# Nu2031.net
KiCad netlist of a schematic drawn in EAGLE
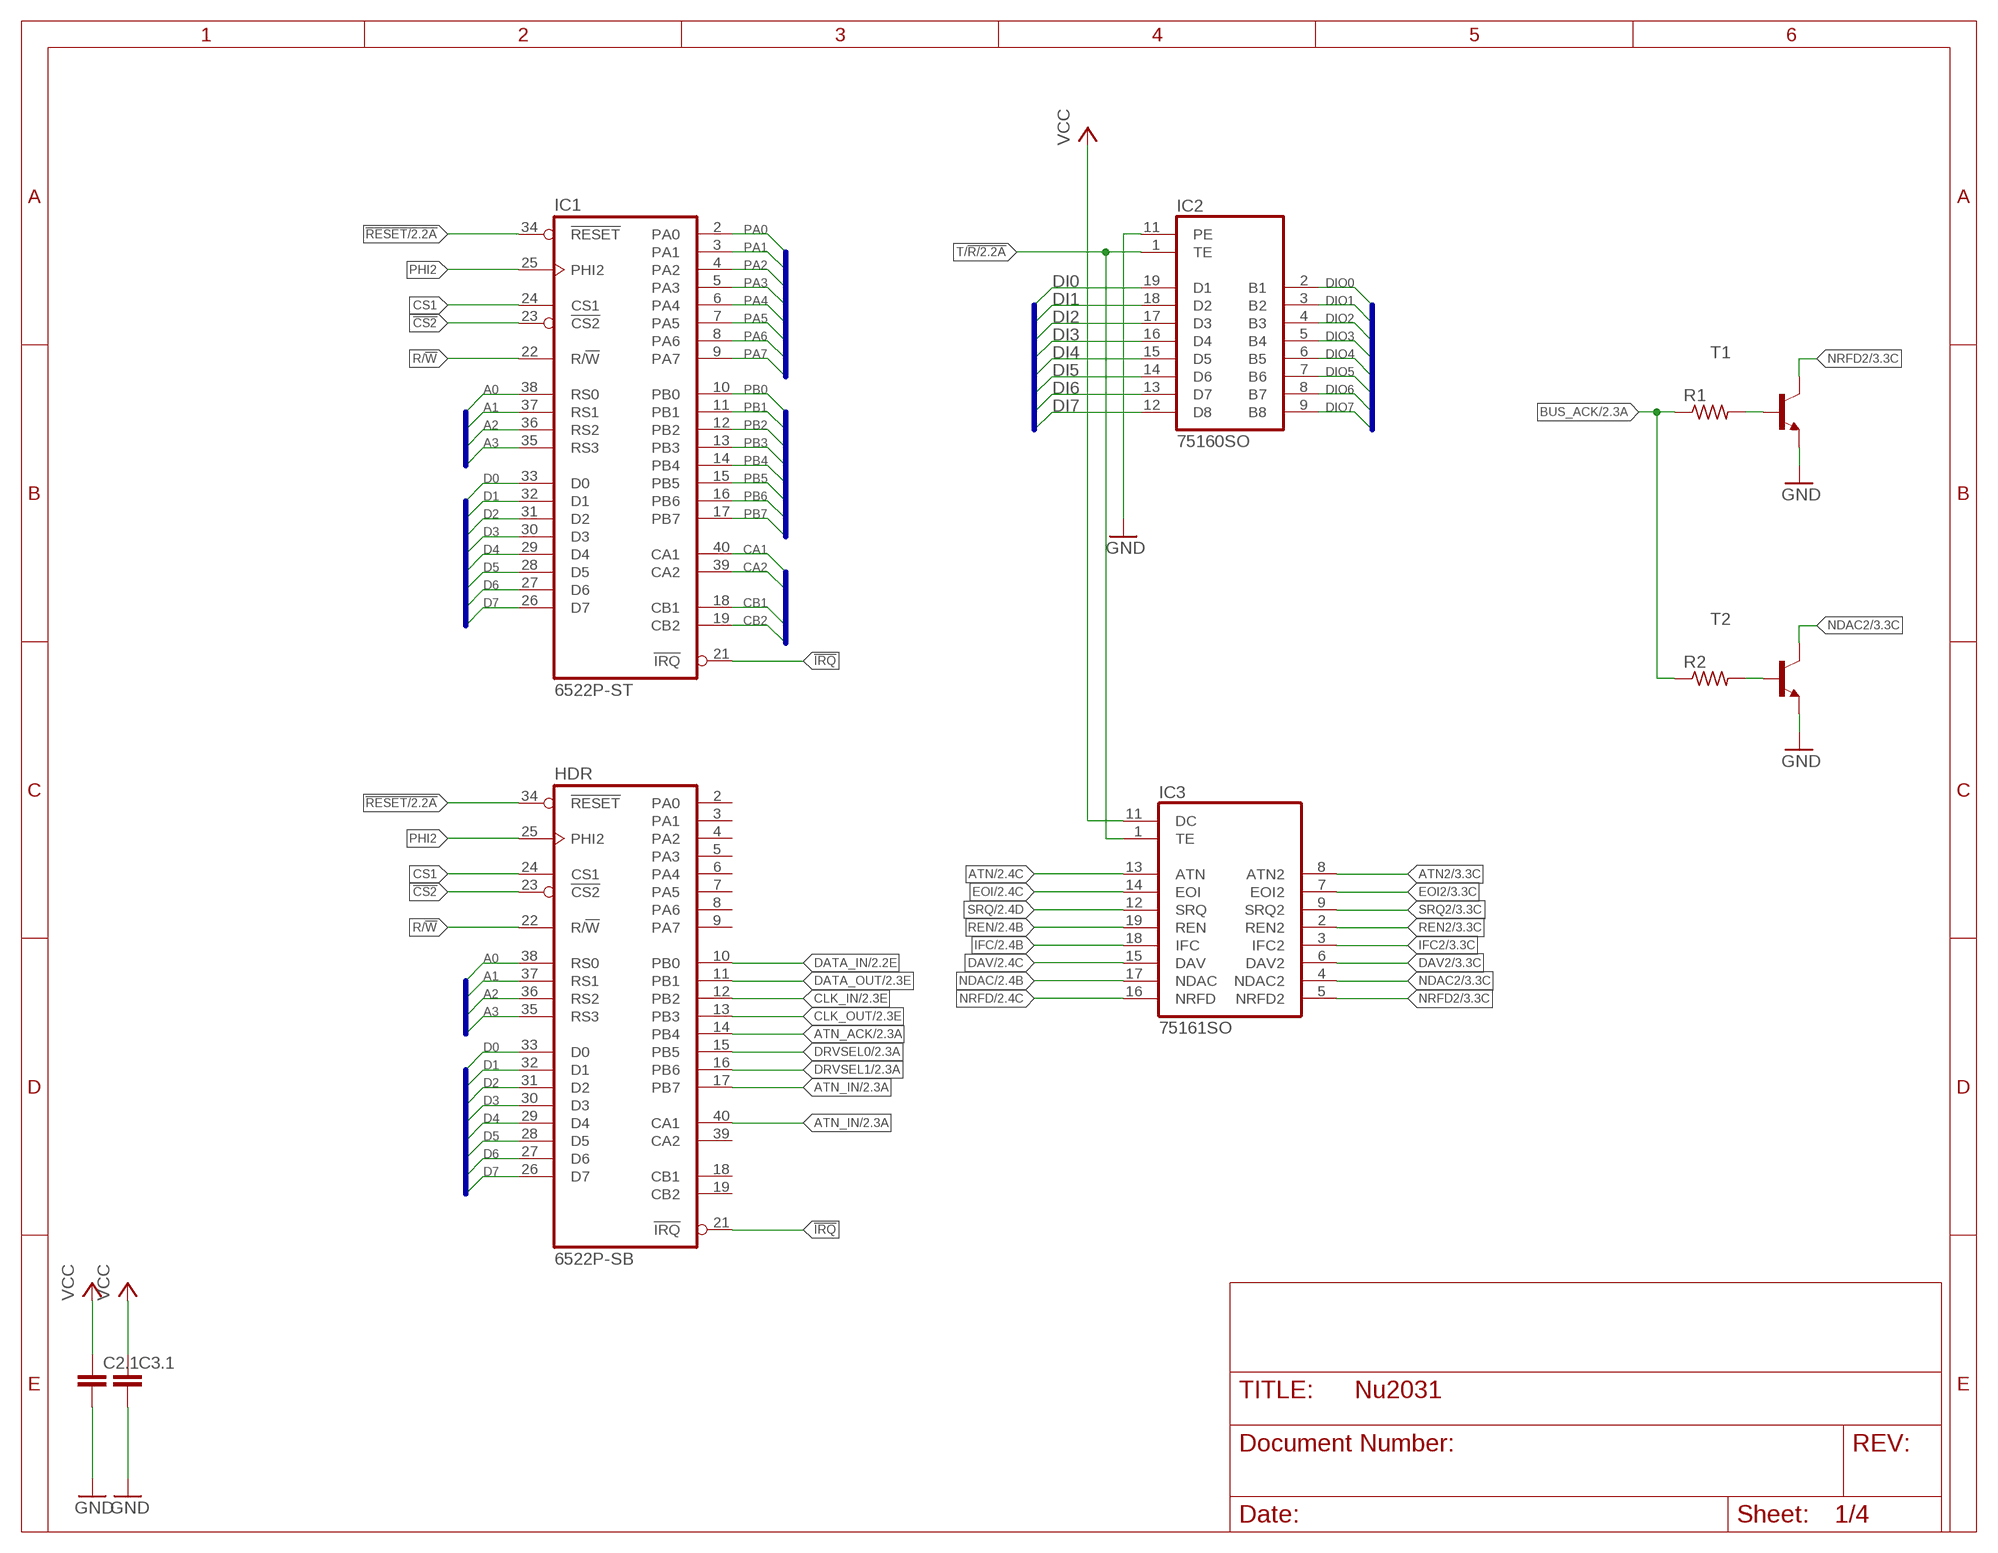
[diagram p0: schematic, sheet 1]
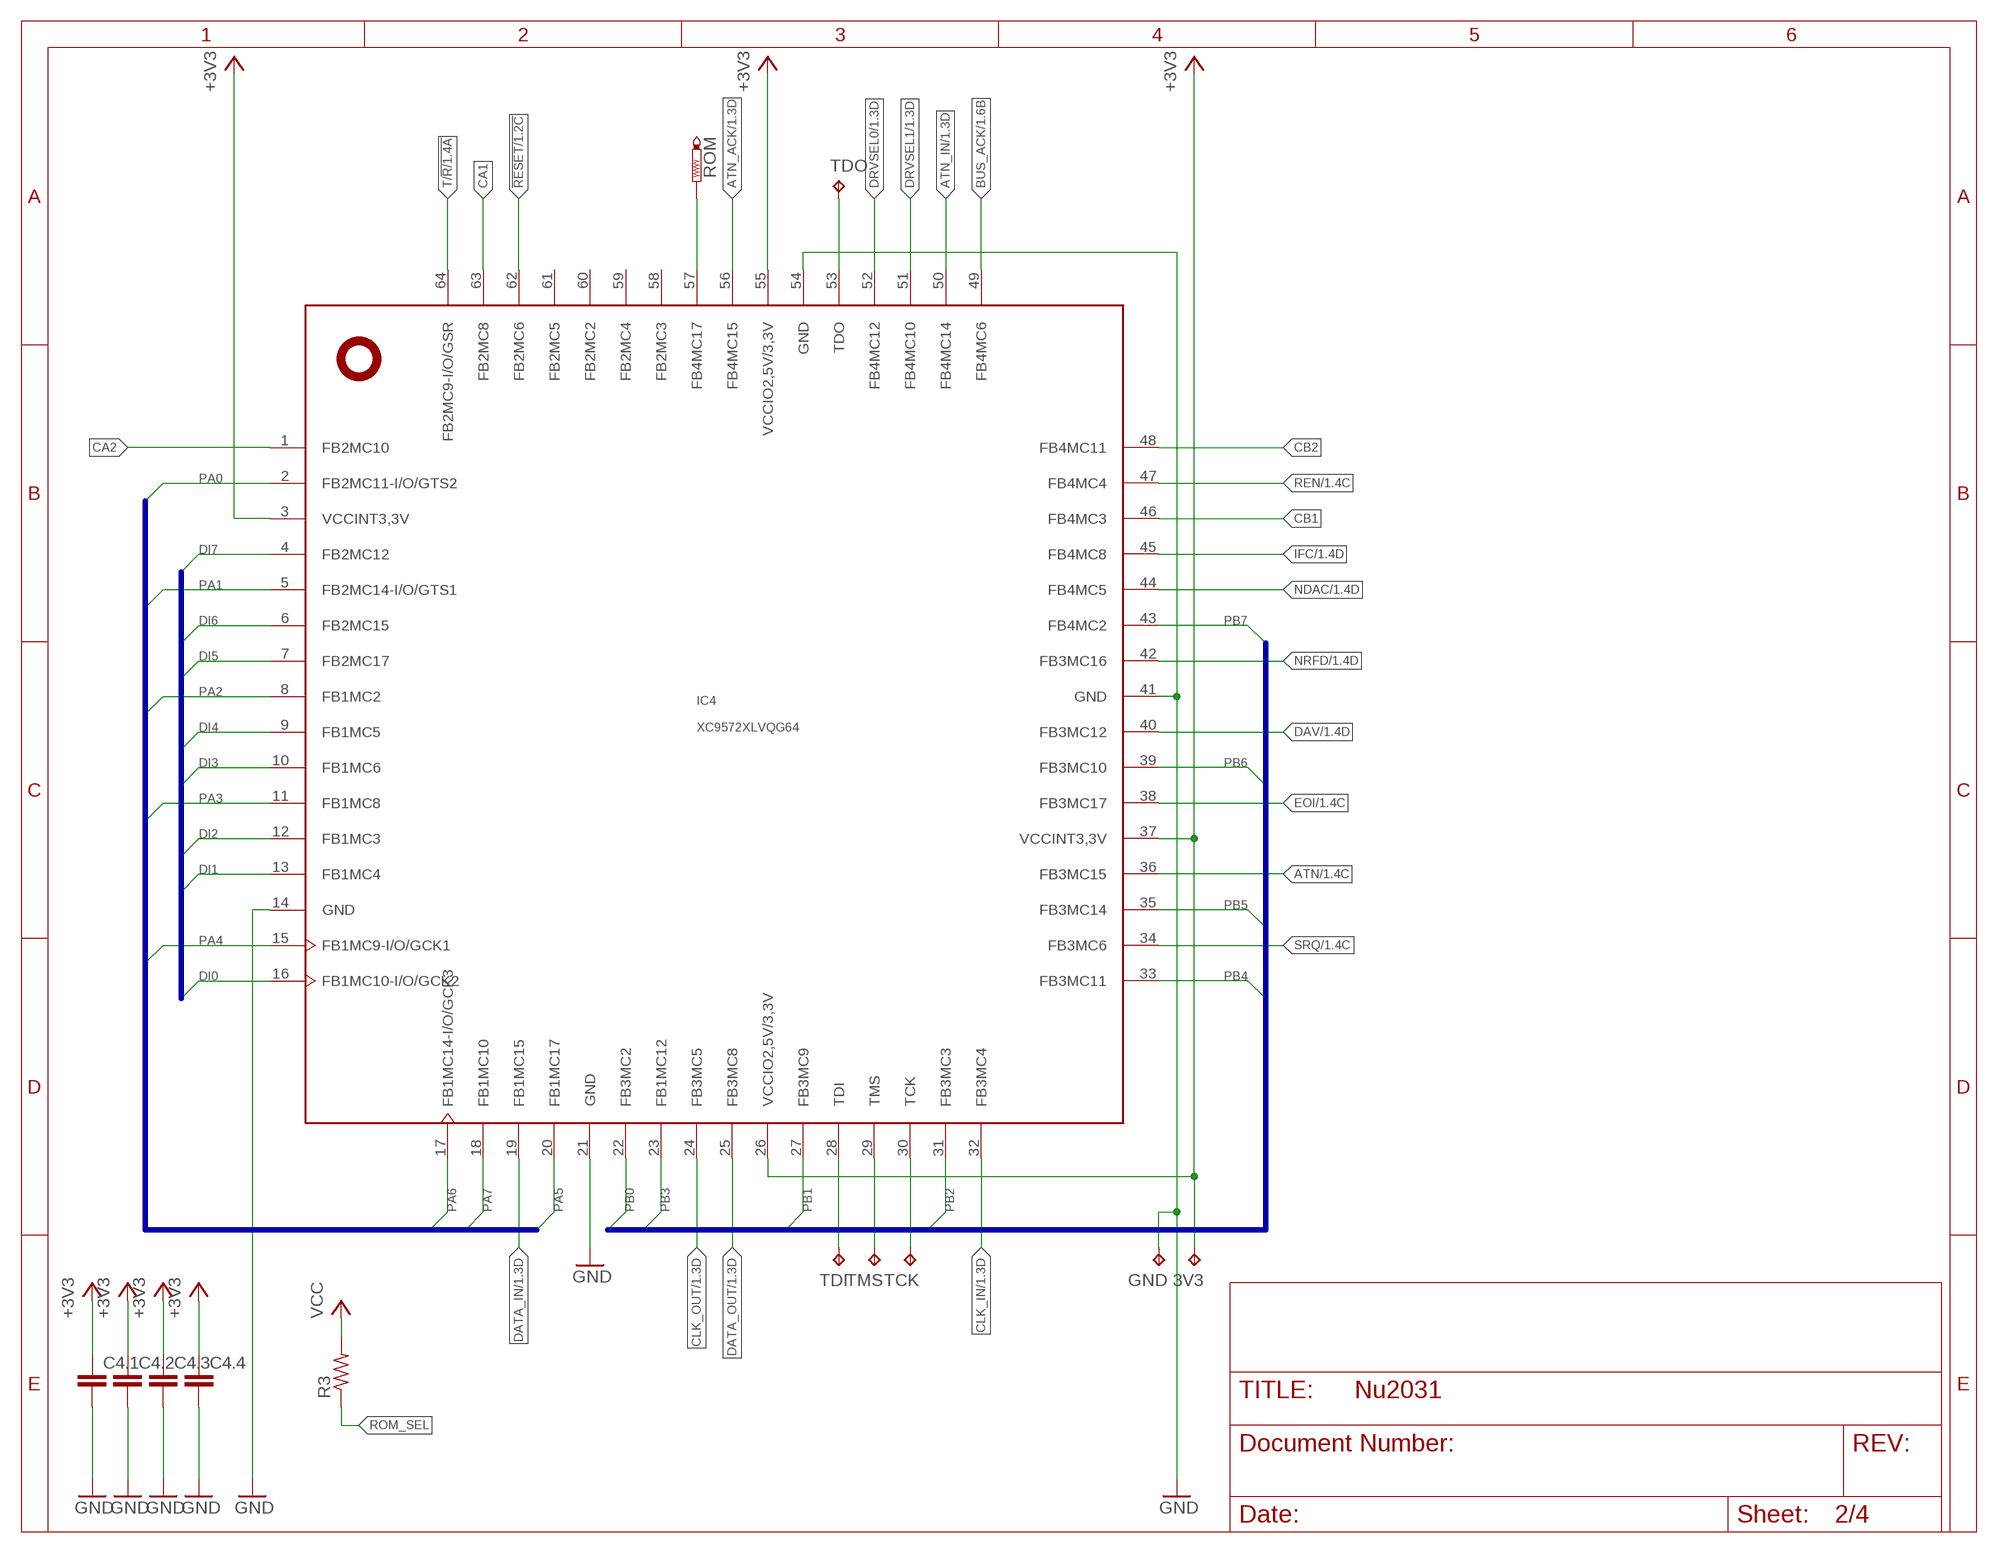
[diagram p1: schematic, sheet 2]
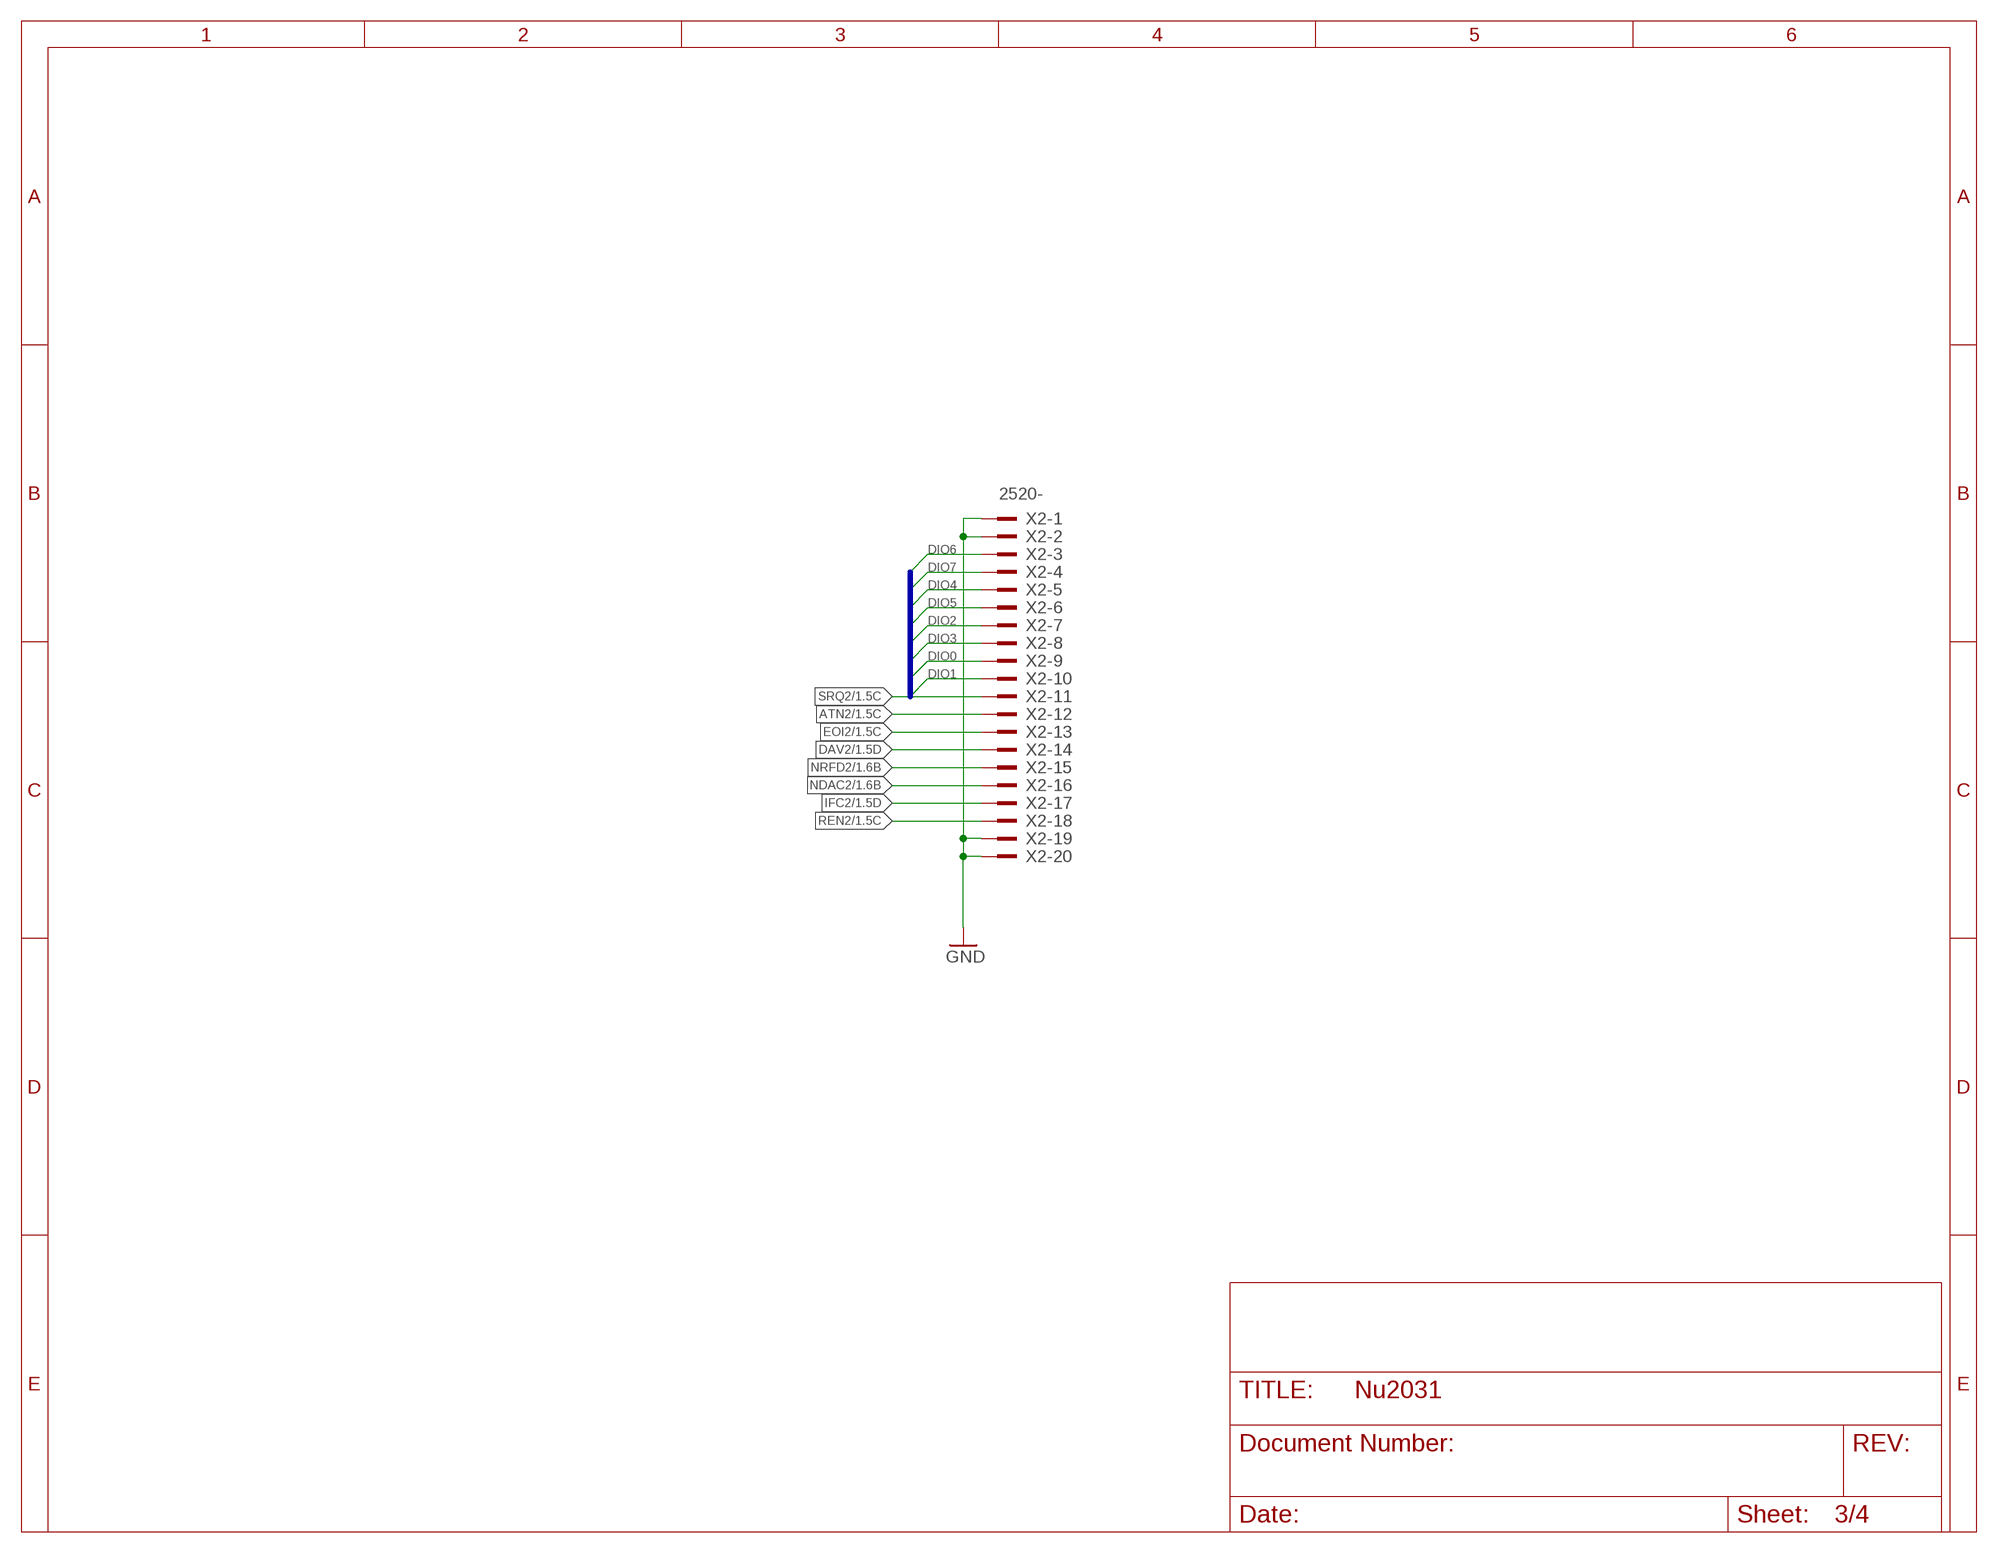
[diagram p2: schematic, sheet 3]
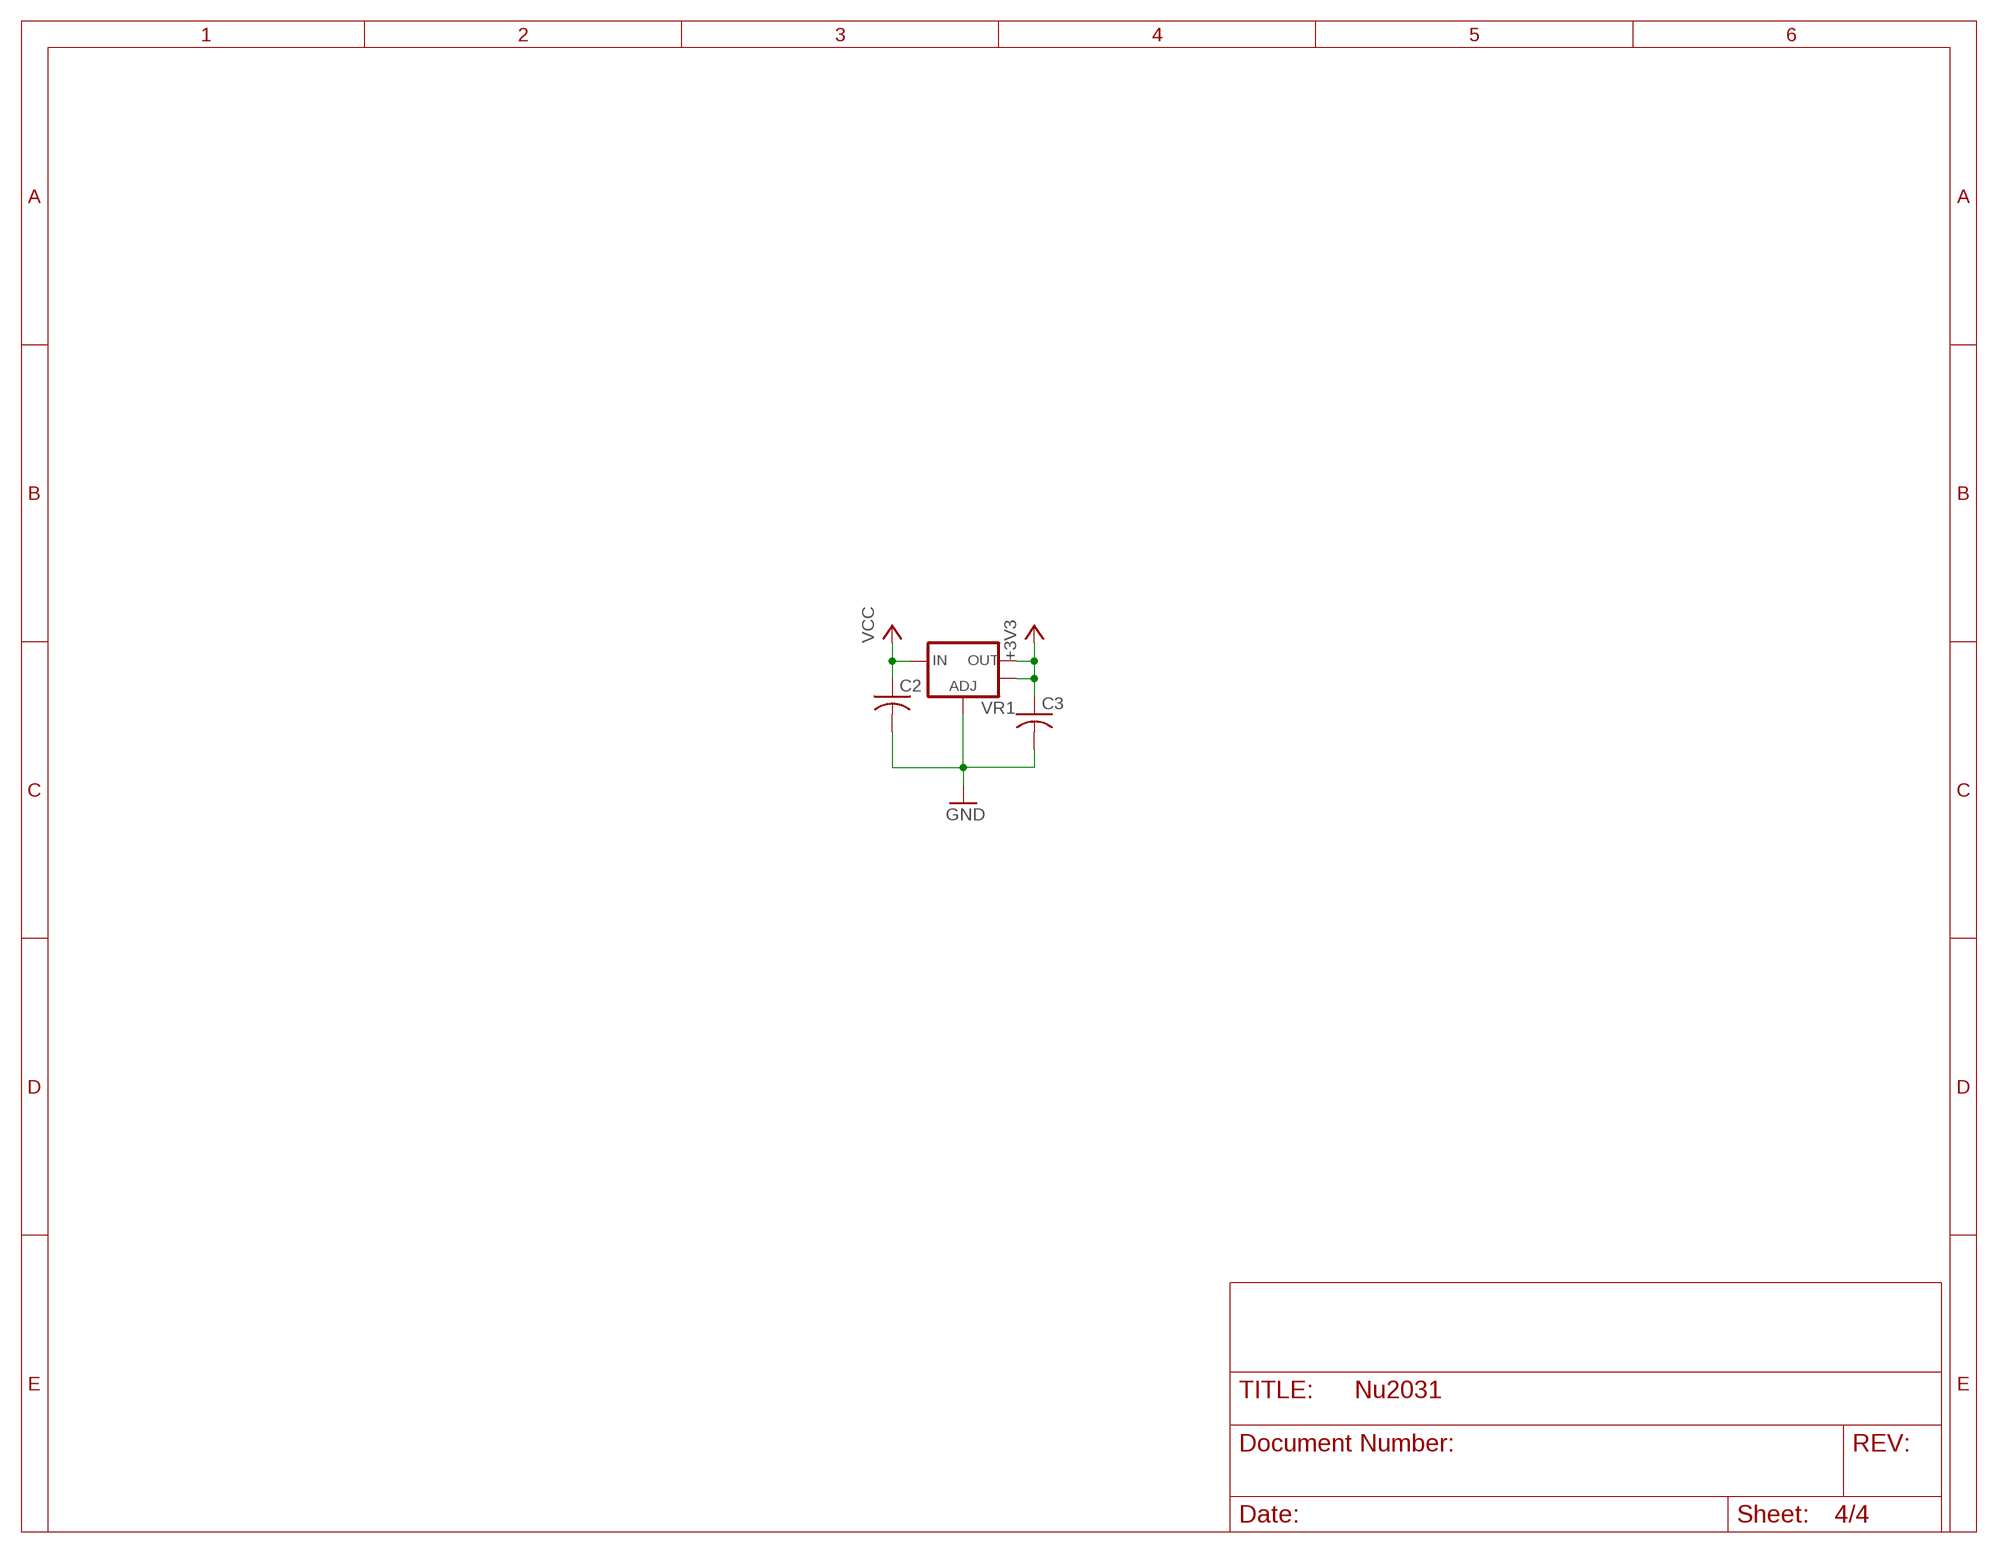
[diagram p3: schematic, sheet 4]

(export (version "E")
  (design (tool "Eeschema 10.0.6"))
  (components
    (comp (ref "X2")
      (value "2520-")
      (footprint "eagle-import:PAK100_2500-20")
      (libsource (lib "eagle-import") (part "2520-"))
    )
    (comp (ref "C2.1")
      (value "C-EUC0402")
      (footprint "eagle-import:C0402")
      (libsource (lib "eagle-import") (part "C-EUC0402"))
    )
    (comp (ref "C3.1")
      (value "C-EUC0402")
      (footprint "eagle-import:C0402")
      (libsource (lib "eagle-import") (part "C-EUC0402"))
    )
    (comp (ref "HDR")
      (value "6522P-SB")
      (footprint "eagle-import:DIL40-SMD-REVERSE")
      (libsource (lib "eagle-import") (part "6522P-SB"))
    )
    (comp (ref "IC1")
      (value "6522P-ST")
      (footprint "eagle-import:DIL40-SMD")
      (libsource (lib "eagle-import") (part "6522P-ST"))
    )
    (comp (ref "IC2")
      (value "75160SO")
      (footprint "eagle-import:SO20L")
      (libsource (lib "eagle-import") (part "75160SO"))
    )
    (comp (ref "IC3")
      (value "75161SO")
      (footprint "eagle-import:SO20L")
      (libsource (lib "eagle-import") (part "75161SO"))
    )
    (comp (ref "R1")
      (value "R-US_R0402")
      (footprint "eagle-import:R0402")
      (libsource (lib "eagle-import") (part "R-US_R0402"))
    )
    (comp (ref "R2")
      (value "R-US_R0402")
      (footprint "eagle-import:R0402")
      (libsource (lib "eagle-import") (part "R-US_R0402"))
    )
    (comp (ref "T1")
      (value "MMBT3904LT1-NPN-SOT23-BEC")
      (footprint "eagle-import:SOT23-BEC")
      (libsource (lib "eagle-import") (part "-NPN-SOT23-BECMMBT3904LT1"))
    )
    (comp (ref "T2")
      (value "MMBT3904LT1-NPN-SOT23-BEC")
      (footprint "eagle-import:SOT23-BEC")
      (libsource (lib "eagle-import") (part "-NPN-SOT23-BECMMBT3904LT1"))
    )
    (comp (ref "C2")
      (value "C-USC0805")
      (footprint "eagle-import:C0805")
      (libsource (lib "eagle-import") (part "C-USC0805"))
    )
    (comp (ref "C3")
      (value "C-USC0805")
      (footprint "eagle-import:C0805")
      (libsource (lib "eagle-import") (part "C-USC0805"))
    )
    (comp (ref "VR1")
      (value "V_REG_LM1117SOT223")
      (footprint "eagle-import:SOT223")
      (libsource (lib "eagle-import") (part "V_REG_LM1117SOT223"))
    )
    (comp (ref "3V3")
      (value "TPTP10R")
      (footprint "eagle-import:TP10R")
      (libsource (lib "eagle-import") (part "TPTP10R"))
    )
    (comp (ref "C4.1")
      (value "C-EUC0402")
      (footprint "eagle-import:C0402")
      (libsource (lib "eagle-import") (part "C-EUC0402"))
    )
    (comp (ref "C4.2")
      (value "C-EUC0402")
      (footprint "eagle-import:C0402")
      (libsource (lib "eagle-import") (part "C-EUC0402"))
    )
    (comp (ref "C4.3")
      (value "C-EUC0402")
      (footprint "eagle-import:C0402")
      (libsource (lib "eagle-import") (part "C-EUC0402"))
    )
    (comp (ref "C4.4")
      (value "C-EUC0402")
      (footprint "eagle-import:C0402")
      (libsource (lib "eagle-import") (part "C-EUC0402"))
    )
    (comp (ref "GND")
      (value "TPTP10R")
      (footprint "eagle-import:TP10R")
      (libsource (lib "eagle-import") (part "TPTP10R"))
    )
    (comp (ref "IC4")
      (value "XC9572XLVQG64")
      (footprint "eagle-import:VQFP64")
      (libsource (lib "eagle-import") (part "XC9572XLVQG64"))
    )
    (comp (ref "R3")
      (value "R-US_R0402")
      (footprint "eagle-import:R0402")
      (libsource (lib "eagle-import") (part "R-US_R0402"))
    )
    (comp (ref "ROM")
      (value "PTR1B1,27")
      (footprint "eagle-import:B1,27")
      (libsource (lib "eagle-import") (part "PTR1B1,27"))
    )
    (comp (ref "TCK")
      (value "TPTP10R")
      (footprint "eagle-import:TP10R")
      (libsource (lib "eagle-import") (part "TPTP10R"))
    )
    (comp (ref "TDI")
      (value "TPTP10R")
      (footprint "eagle-import:TP10R")
      (libsource (lib "eagle-import") (part "TPTP10R"))
    )
    (comp (ref "TDO")
      (value "TPTP10R")
      (footprint "eagle-import:TP10R")
      (libsource (lib "eagle-import") (part "TPTP10R"))
    )
    (comp (ref "TMS")
      (value "TPTP10R")
      (footprint "eagle-import:TP10R")
      (libsource (lib "eagle-import") (part "TPTP10R"))
    )
  )
  (nets
    (net (code "1") (name "+3V3") (class "Default")
      (node (ref "3V3") (pin "TP") (pinfunction "TP_TP") (pintype "input"))
      (node (ref "C3") (pin "1") (pinfunction "1_1") (pintype "passive"))
      (node (ref "C4.1") (pin "1") (pinfunction "1_1") (pintype "passive"))
      (node (ref "C4.2") (pin "1") (pinfunction "1_1") (pintype "passive"))
      (node (ref "C4.3") (pin "1") (pinfunction "1_1") (pintype "passive"))
      (node (ref "C4.4") (pin "1") (pinfunction "1_1") (pintype "passive"))
      (node (ref "IC4") (pin "26") (pinfunction "VCCIO2,5V/3,3V_26") (pintype "power_in"))
      (node (ref "IC4") (pin "3") (pinfunction "VCCINT3,3V_3") (pintype "power_in"))
      (node (ref "IC4") (pin "37") (pinfunction "VCCINT3,3V_37") (pintype "power_in"))
      (node (ref "IC4") (pin "55") (pinfunction "VCCIO2,5V/3,3V_55") (pintype "power_in"))
      (node (ref "VR1") (pin "2") (pinfunction "OUT_2") (pintype "output"))
      (node (ref "VR1") (pin "4") (pinfunction "OUT_4") (pintype "output"))
    )
    (net (code "2") (name "A0") (class "Default")
      (node (ref "HDR") (pin "38") (pinfunction "RS0_38") (pintype "input"))
      (node (ref "IC1") (pin "38") (pinfunction "RS0_38") (pintype "input"))
    )
    (net (code "3") (name "A1") (class "Default")
      (node (ref "HDR") (pin "37") (pinfunction "RS1_37") (pintype "input"))
      (node (ref "IC1") (pin "37") (pinfunction "RS1_37") (pintype "input"))
    )
    (net (code "4") (name "A2") (class "Default")
      (node (ref "HDR") (pin "36") (pinfunction "RS2_36") (pintype "input"))
      (node (ref "IC1") (pin "36") (pinfunction "RS2_36") (pintype "input"))
    )
    (net (code "5") (name "A3") (class "Default")
      (node (ref "HDR") (pin "35") (pinfunction "RS3_35") (pintype "input"))
      (node (ref "IC1") (pin "35") (pinfunction "RS3_35") (pintype "input"))
    )
    (net (code "6") (name "ATN") (class "Default")
      (node (ref "IC3") (pin "13") (pinfunction "ATN_13") (pintype "bidirectional"))
      (node (ref "IC4") (pin "36") (pinfunction "FB3MC15_36") (pintype "bidirectional"))
    )
    (net (code "7") (name "ATN2") (class "Default")
      (node (ref "IC3") (pin "8") (pinfunction "ATN2_8") (pintype "bidirectional"))
      (node (ref "X2") (pin "12") (pinfunction "KL_12") (pintype "passive"))
    )
    (net (code "8") (name "ATN_ACK") (class "Default")
      (node (ref "HDR") (pin "14") (pinfunction "PB4_14") (pintype "bidirectional"))
      (node (ref "IC4") (pin "56") (pinfunction "FB4MC15_56") (pintype "bidirectional"))
    )
    (net (code "9") (name "ATN_IN") (class "Default")
      (node (ref "HDR") (pin "17") (pinfunction "PB7_17") (pintype "bidirectional"))
      (node (ref "HDR") (pin "40") (pinfunction "CA1_40") (pintype "input"))
      (node (ref "IC4") (pin "50") (pinfunction "FB4MC14_50") (pintype "bidirectional"))
    )
    (net (code "10") (name "BUS_ACK") (class "Default")
      (node (ref "IC4") (pin "49") (pinfunction "FB4MC6_49") (pintype "bidirectional"))
      (node (ref "R1") (pin "1") (pinfunction "1_1") (pintype "passive"))
      (node (ref "R2") (pin "1") (pinfunction "1_1") (pintype "passive"))
    )
    (net (code "11") (name "CA1") (class "Default")
      (node (ref "IC1") (pin "40") (pinfunction "CA1_40") (pintype "input"))
      (node (ref "IC4") (pin "63") (pinfunction "FB2MC8_63") (pintype "bidirectional"))
    )
    (net (code "12") (name "CA2") (class "Default")
      (node (ref "IC1") (pin "39") (pinfunction "CA2_39") (pintype "bidirectional"))
      (node (ref "IC4") (pin "1") (pinfunction "FB2MC10_1") (pintype "bidirectional"))
    )
    (net (code "13") (name "CB1") (class "Default")
      (node (ref "IC1") (pin "18") (pinfunction "CB1_18") (pintype "input"))
      (node (ref "IC4") (pin "46") (pinfunction "FB4MC3_46") (pintype "bidirectional"))
    )
    (net (code "14") (name "CB2") (class "Default")
      (node (ref "IC1") (pin "19") (pinfunction "CB2_19") (pintype "bidirectional"))
      (node (ref "IC4") (pin "48") (pinfunction "FB4MC11_48") (pintype "bidirectional"))
    )
    (net (code "15") (name "CLK_IN") (class "Default")
      (node (ref "HDR") (pin "12") (pinfunction "PB2_12") (pintype "bidirectional"))
      (node (ref "IC4") (pin "32") (pinfunction "FB3MC4_32") (pintype "bidirectional"))
    )
    (net (code "16") (name "CLK_OUT") (class "Default")
      (node (ref "HDR") (pin "13") (pinfunction "PB3_13") (pintype "bidirectional"))
      (node (ref "IC4") (pin "24") (pinfunction "FB3MC5_24") (pintype "bidirectional"))
    )
    (net (code "17") (name "CS1") (class "Default")
      (node (ref "HDR") (pin "24") (pinfunction "CS1_24") (pintype "input"))
      (node (ref "IC1") (pin "24") (pinfunction "CS1_24") (pintype "input"))
    )
    (net (code "18") (name "D0") (class "Default")
      (node (ref "HDR") (pin "33") (pinfunction "D0_33") (pintype "bidirectional"))
      (node (ref "IC1") (pin "33") (pinfunction "D0_33") (pintype "bidirectional"))
    )
    (net (code "19") (name "D1") (class "Default")
      (node (ref "HDR") (pin "32") (pinfunction "D1_32") (pintype "bidirectional"))
      (node (ref "IC1") (pin "32") (pinfunction "D1_32") (pintype "bidirectional"))
    )
    (net (code "20") (name "D2") (class "Default")
      (node (ref "HDR") (pin "31") (pinfunction "D2_31") (pintype "bidirectional"))
      (node (ref "IC1") (pin "31") (pinfunction "D2_31") (pintype "bidirectional"))
    )
    (net (code "21") (name "D3") (class "Default")
      (node (ref "HDR") (pin "30") (pinfunction "D3_30") (pintype "bidirectional"))
      (node (ref "IC1") (pin "30") (pinfunction "D3_30") (pintype "bidirectional"))
    )
    (net (code "22") (name "D4") (class "Default")
      (node (ref "HDR") (pin "29") (pinfunction "D4_29") (pintype "bidirectional"))
      (node (ref "IC1") (pin "29") (pinfunction "D4_29") (pintype "bidirectional"))
    )
    (net (code "23") (name "D5") (class "Default")
      (node (ref "HDR") (pin "28") (pinfunction "D5_28") (pintype "bidirectional"))
      (node (ref "IC1") (pin "28") (pinfunction "D5_28") (pintype "bidirectional"))
    )
    (net (code "24") (name "D6") (class "Default")
      (node (ref "HDR") (pin "27") (pinfunction "D6_27") (pintype "bidirectional"))
      (node (ref "IC1") (pin "27") (pinfunction "D6_27") (pintype "bidirectional"))
    )
    (net (code "25") (name "D7") (class "Default")
      (node (ref "HDR") (pin "26") (pinfunction "D7_26") (pintype "bidirectional"))
      (node (ref "IC1") (pin "26") (pinfunction "D7_26") (pintype "bidirectional"))
    )
    (net (code "26") (name "DATA_IN") (class "Default")
      (node (ref "HDR") (pin "10") (pinfunction "PB0_10") (pintype "bidirectional"))
      (node (ref "IC4") (pin "19") (pinfunction "FB1MC15_19") (pintype "bidirectional"))
    )
    (net (code "27") (name "DATA_OUT") (class "Default")
      (node (ref "HDR") (pin "11") (pinfunction "PB1_11") (pintype "bidirectional"))
      (node (ref "IC4") (pin "25") (pinfunction "FB3MC8_25") (pintype "bidirectional"))
    )
    (net (code "28") (name "DAV") (class "Default")
      (node (ref "IC3") (pin "15") (pinfunction "DAV_15") (pintype "bidirectional"))
      (node (ref "IC4") (pin "40") (pinfunction "FB3MC12_40") (pintype "bidirectional"))
    )
    (net (code "29") (name "DAV2") (class "Default")
      (node (ref "IC3") (pin "6") (pinfunction "DAV2_6") (pintype "bidirectional"))
      (node (ref "X2") (pin "14") (pinfunction "KL_14") (pintype "passive"))
    )
    (net (code "30") (name "DI0") (class "Default")
      (node (ref "IC2") (pin "19") (pinfunction "D1_19") (pintype "bidirectional"))
      (node (ref "IC4") (pin "16") (pinfunction "FB1MC10-I/O/GCK2_16") (pintype "bidirectional"))
    )
    (net (code "31") (name "DI1") (class "Default")
      (node (ref "IC2") (pin "18") (pinfunction "D2_18") (pintype "bidirectional"))
      (node (ref "IC4") (pin "13") (pinfunction "FB1MC4_13") (pintype "bidirectional"))
    )
    (net (code "32") (name "DI2") (class "Default")
      (node (ref "IC2") (pin "17") (pinfunction "D3_17") (pintype "bidirectional"))
      (node (ref "IC4") (pin "12") (pinfunction "FB1MC3_12") (pintype "bidirectional"))
    )
    (net (code "33") (name "DI3") (class "Default")
      (node (ref "IC2") (pin "16") (pinfunction "D4_16") (pintype "bidirectional"))
      (node (ref "IC4") (pin "10") (pinfunction "FB1MC6_10") (pintype "bidirectional"))
    )
    (net (code "34") (name "DI4") (class "Default")
      (node (ref "IC2") (pin "15") (pinfunction "D5_15") (pintype "bidirectional"))
      (node (ref "IC4") (pin "9") (pinfunction "FB1MC5_9") (pintype "bidirectional"))
    )
    (net (code "35") (name "DI5") (class "Default")
      (node (ref "IC2") (pin "14") (pinfunction "D6_14") (pintype "bidirectional"))
      (node (ref "IC4") (pin "7") (pinfunction "FB2MC17_7") (pintype "bidirectional"))
    )
    (net (code "36") (name "DI6") (class "Default")
      (node (ref "IC2") (pin "13") (pinfunction "D7_13") (pintype "bidirectional"))
      (node (ref "IC4") (pin "6") (pinfunction "FB2MC15_6") (pintype "bidirectional"))
    )
    (net (code "37") (name "DI7") (class "Default")
      (node (ref "IC2") (pin "12") (pinfunction "D8_12") (pintype "bidirectional"))
      (node (ref "IC4") (pin "4") (pinfunction "FB2MC12_4") (pintype "bidirectional"))
    )
    (net (code "38") (name "DIO0") (class "Default")
      (node (ref "IC2") (pin "2") (pinfunction "B1_2") (pintype "bidirectional"))
      (node (ref "X2") (pin "9") (pinfunction "KL_9") (pintype "passive"))
    )
    (net (code "39") (name "DIO1") (class "Default")
      (node (ref "IC2") (pin "3") (pinfunction "B2_3") (pintype "bidirectional"))
      (node (ref "X2") (pin "10") (pinfunction "KL_10") (pintype "passive"))
    )
    (net (code "40") (name "DIO2") (class "Default")
      (node (ref "IC2") (pin "4") (pinfunction "B3_4") (pintype "bidirectional"))
      (node (ref "X2") (pin "7") (pinfunction "KL_7") (pintype "passive"))
    )
    (net (code "41") (name "DIO3") (class "Default")
      (node (ref "IC2") (pin "5") (pinfunction "B4_5") (pintype "bidirectional"))
      (node (ref "X2") (pin "8") (pinfunction "KL_8") (pintype "passive"))
    )
    (net (code "42") (name "DIO4") (class "Default")
      (node (ref "IC2") (pin "6") (pinfunction "B5_6") (pintype "bidirectional"))
      (node (ref "X2") (pin "5") (pinfunction "KL_5") (pintype "passive"))
    )
    (net (code "43") (name "DIO5") (class "Default")
      (node (ref "IC2") (pin "7") (pinfunction "B6_7") (pintype "bidirectional"))
      (node (ref "X2") (pin "6") (pinfunction "KL_6") (pintype "passive"))
    )
    (net (code "44") (name "DIO6") (class "Default")
      (node (ref "IC2") (pin "8") (pinfunction "B7_8") (pintype "bidirectional"))
      (node (ref "X2") (pin "3") (pinfunction "KL_3") (pintype "passive"))
    )
    (net (code "45") (name "DIO7") (class "Default")
      (node (ref "IC2") (pin "9") (pinfunction "B8_9") (pintype "bidirectional"))
      (node (ref "X2") (pin "4") (pinfunction "KL_4") (pintype "passive"))
    )
    (net (code "46") (name "DRVSEL0") (class "Default")
      (node (ref "HDR") (pin "15") (pinfunction "PB5_15") (pintype "bidirectional"))
      (node (ref "IC4") (pin "52") (pinfunction "FB4MC12_52") (pintype "bidirectional"))
    )
    (net (code "47") (name "DRVSEL1") (class "Default")
      (node (ref "HDR") (pin "16") (pinfunction "PB6_16") (pintype "bidirectional"))
      (node (ref "IC4") (pin "51") (pinfunction "FB4MC10_51") (pintype "bidirectional"))
    )
    (net (code "48") (name "EOI") (class "Default")
      (node (ref "IC3") (pin "14") (pinfunction "EOI_14") (pintype "bidirectional"))
      (node (ref "IC4") (pin "38") (pinfunction "FB3MC17_38") (pintype "bidirectional"))
    )
    (net (code "49") (name "EOI2") (class "Default")
      (node (ref "IC3") (pin "7") (pinfunction "EOI2_7") (pintype "bidirectional"))
      (node (ref "X2") (pin "13") (pinfunction "KL_13") (pintype "passive"))
    )
    (net (code "50") (name "GND") (class "Default")
      (node (ref "C2") (pin "2") (pinfunction "2_2") (pintype "passive"))
      (node (ref "C2.1") (pin "2") (pinfunction "2_2") (pintype "passive"))
      (node (ref "C3") (pin "2") (pinfunction "2_2") (pintype "passive"))
      (node (ref "C3.1") (pin "2") (pinfunction "2_2") (pintype "passive"))
      (node (ref "C4.1") (pin "2") (pinfunction "2_2") (pintype "passive"))
      (node (ref "C4.2") (pin "2") (pinfunction "2_2") (pintype "passive"))
      (node (ref "C4.3") (pin "2") (pinfunction "2_2") (pintype "passive"))
      (node (ref "C4.4") (pin "2") (pinfunction "2_2") (pintype "passive"))
      (node (ref "GND") (pin "TP") (pinfunction "TP_TP") (pintype "input"))
      (node (ref "IC2") (pin "11") (pinfunction "PE_11") (pintype "input"))
      (node (ref "IC4") (pin "14") (pinfunction "GND_14") (pintype "power_in"))
      (node (ref "IC4") (pin "21") (pinfunction "GND_21") (pintype "power_in"))
      (node (ref "IC4") (pin "41") (pinfunction "GND_41") (pintype "power_in"))
      (node (ref "IC4") (pin "54") (pinfunction "GND_54") (pintype "power_in"))
      (node (ref "T1") (pin "E") (pinfunction "E_E") (pintype "passive"))
      (node (ref "T2") (pin "E") (pinfunction "E_E") (pintype "passive"))
      (node (ref "VR1") (pin "1") (pinfunction "ADJ_1") (pintype "input"))
      (node (ref "X2") (pin "1") (pinfunction "KL_1") (pintype "passive"))
      (node (ref "X2") (pin "19") (pinfunction "KL_19") (pintype "passive"))
      (node (ref "X2") (pin "2") (pinfunction "KL_2") (pintype "passive"))
      (node (ref "X2") (pin "20") (pinfunction "KL_20") (pintype "passive"))
    )
    (net (code "51") (name "IFC") (class "Default")
      (node (ref "IC3") (pin "18") (pinfunction "IFC_18") (pintype "bidirectional"))
      (node (ref "IC4") (pin "45") (pinfunction "FB4MC8_45") (pintype "bidirectional"))
    )
    (net (code "52") (name "IFC2") (class "Default")
      (node (ref "IC3") (pin "3") (pinfunction "IFC2_3") (pintype "bidirectional"))
      (node (ref "X2") (pin "17") (pinfunction "KL_17") (pintype "passive"))
    )
    (net (code "53") (name "NDAC") (class "Default")
      (node (ref "IC3") (pin "17") (pinfunction "NDAC_17") (pintype "bidirectional"))
      (node (ref "IC4") (pin "44") (pinfunction "FB4MC5_44") (pintype "bidirectional"))
    )
    (net (code "54") (name "NDAC2") (class "Default")
      (node (ref "IC3") (pin "4") (pinfunction "NDAC2_4") (pintype "bidirectional"))
      (node (ref "T2") (pin "C") (pinfunction "C_C") (pintype "passive"))
      (node (ref "X2") (pin "16") (pinfunction "KL_16") (pintype "passive"))
    )
    (net (code "55") (name "NRFD") (class "Default")
      (node (ref "IC3") (pin "16") (pinfunction "NRFD_16") (pintype "bidirectional"))
      (node (ref "IC4") (pin "42") (pinfunction "FB3MC16_42") (pintype "bidirectional"))
    )
    (net (code "56") (name "NRFD2") (class "Default")
      (node (ref "IC3") (pin "5") (pinfunction "NRFD2_5") (pintype "bidirectional"))
      (node (ref "T1") (pin "C") (pinfunction "C_C") (pintype "passive"))
      (node (ref "X2") (pin "15") (pinfunction "KL_15") (pintype "passive"))
    )
    (net (code "57") (name "Net-(IC4-TCK)") (class "Default")
      (node (ref "IC4") (pin "30") (pinfunction "TCK_30") (pintype "bidirectional"))
      (node (ref "TCK") (pin "TP") (pinfunction "TP_TP") (pintype "input"))
    )
    (net (code "58") (name "Net-(IC4-TDI)") (class "Default")
      (node (ref "IC4") (pin "28") (pinfunction "TDI_28") (pintype "bidirectional"))
      (node (ref "TDI") (pin "TP") (pinfunction "TP_TP") (pintype "input"))
    )
    (net (code "59") (name "Net-(IC4-TDO)") (class "Default")
      (node (ref "IC4") (pin "53") (pinfunction "TDO_53") (pintype "bidirectional"))
      (node (ref "TDO") (pin "TP") (pinfunction "TP_TP") (pintype "input"))
    )
    (net (code "60") (name "Net-(IC4-TMS)") (class "Default")
      (node (ref "IC4") (pin "29") (pinfunction "TMS_29") (pintype "bidirectional"))
      (node (ref "TMS") (pin "TP") (pinfunction "TP_TP") (pintype "input"))
    )
    (net (code "61") (name "Net-(R1-Pad2)") (class "Default")
      (node (ref "R1") (pin "2") (pinfunction "2_2") (pintype "passive"))
      (node (ref "T1") (pin "B") (pinfunction "B_B") (pintype "passive"))
    )
    (net (code "62") (name "Net-(R2-Pad2)") (class "Default")
      (node (ref "R2") (pin "2") (pinfunction "2_2") (pintype "passive"))
      (node (ref "T2") (pin "B") (pinfunction "B_B") (pintype "passive"))
    )
    (net (code "63") (name "PA0") (class "Default")
      (node (ref "IC1") (pin "2") (pinfunction "PA0_2") (pintype "bidirectional"))
      (node (ref "IC4") (pin "2") (pinfunction "FB2MC11-I/O/GTS2_2") (pintype "bidirectional"))
    )
    (net (code "64") (name "PA1") (class "Default")
      (node (ref "IC1") (pin "3") (pinfunction "PA1_3") (pintype "bidirectional"))
      (node (ref "IC4") (pin "5") (pinfunction "FB2MC14-I/O/GTS1_5") (pintype "bidirectional"))
    )
    (net (code "65") (name "PA2") (class "Default")
      (node (ref "IC1") (pin "4") (pinfunction "PA2_4") (pintype "bidirectional"))
      (node (ref "IC4") (pin "8") (pinfunction "FB1MC2_8") (pintype "bidirectional"))
    )
    (net (code "66") (name "PA3") (class "Default")
      (node (ref "IC1") (pin "5") (pinfunction "PA3_5") (pintype "bidirectional"))
      (node (ref "IC4") (pin "11") (pinfunction "FB1MC8_11") (pintype "bidirectional"))
    )
    (net (code "67") (name "PA4") (class "Default")
      (node (ref "IC1") (pin "6") (pinfunction "PA4_6") (pintype "bidirectional"))
      (node (ref "IC4") (pin "15") (pinfunction "FB1MC9-I/O/GCK1_15") (pintype "bidirectional"))
    )
    (net (code "68") (name "PA5") (class "Default")
      (node (ref "IC1") (pin "7") (pinfunction "PA5_7") (pintype "bidirectional"))
      (node (ref "IC4") (pin "20") (pinfunction "FB1MC17_20") (pintype "bidirectional"))
    )
    (net (code "69") (name "PA6") (class "Default")
      (node (ref "IC1") (pin "8") (pinfunction "PA6_8") (pintype "bidirectional"))
      (node (ref "IC4") (pin "17") (pinfunction "FB1MC14-I/O/GCK3_17") (pintype "bidirectional"))
    )
    (net (code "70") (name "PA7") (class "Default")
      (node (ref "IC1") (pin "9") (pinfunction "PA7_9") (pintype "bidirectional"))
      (node (ref "IC4") (pin "18") (pinfunction "FB1MC10_18") (pintype "bidirectional"))
    )
    (net (code "71") (name "PB0") (class "Default")
      (node (ref "IC1") (pin "10") (pinfunction "PB0_10") (pintype "bidirectional"))
      (node (ref "IC4") (pin "22") (pinfunction "FB3MC2_22") (pintype "bidirectional"))
    )
    (net (code "72") (name "PB1") (class "Default")
      (node (ref "IC1") (pin "11") (pinfunction "PB1_11") (pintype "bidirectional"))
      (node (ref "IC4") (pin "27") (pinfunction "FB3MC9_27") (pintype "bidirectional"))
    )
    (net (code "73") (name "PB2") (class "Default")
      (node (ref "IC1") (pin "12") (pinfunction "PB2_12") (pintype "bidirectional"))
      (node (ref "IC4") (pin "31") (pinfunction "FB3MC3_31") (pintype "bidirectional"))
    )
    (net (code "74") (name "PB3") (class "Default")
      (node (ref "IC1") (pin "13") (pinfunction "PB3_13") (pintype "bidirectional"))
      (node (ref "IC4") (pin "23") (pinfunction "FB1MC12_23") (pintype "bidirectional"))
    )
    (net (code "75") (name "PB4") (class "Default")
      (node (ref "IC1") (pin "14") (pinfunction "PB4_14") (pintype "bidirectional"))
      (node (ref "IC4") (pin "33") (pinfunction "FB3MC11_33") (pintype "bidirectional"))
    )
    (net (code "76") (name "PB5") (class "Default")
      (node (ref "IC1") (pin "15") (pinfunction "PB5_15") (pintype "bidirectional"))
      (node (ref "IC4") (pin "35") (pinfunction "FB3MC14_35") (pintype "bidirectional"))
    )
    (net (code "77") (name "PB6") (class "Default")
      (node (ref "IC1") (pin "16") (pinfunction "PB6_16") (pintype "bidirectional"))
      (node (ref "IC4") (pin "39") (pinfunction "FB3MC10_39") (pintype "bidirectional"))
    )
    (net (code "78") (name "PB7") (class "Default")
      (node (ref "IC1") (pin "17") (pinfunction "PB7_17") (pintype "bidirectional"))
      (node (ref "IC4") (pin "43") (pinfunction "FB4MC2_43") (pintype "bidirectional"))
    )
    (net (code "79") (name "PHI2") (class "Default")
      (node (ref "HDR") (pin "25") (pinfunction "PHI2_25") (pintype "input"))
      (node (ref "IC1") (pin "25") (pinfunction "PHI2_25") (pintype "input"))
    )
    (net (code "80") (name "REN") (class "Default")
      (node (ref "IC3") (pin "19") (pinfunction "REN_19") (pintype "bidirectional"))
      (node (ref "IC4") (pin "47") (pinfunction "FB4MC4_47") (pintype "bidirectional"))
    )
    (net (code "81") (name "REN2") (class "Default")
      (node (ref "IC3") (pin "2") (pinfunction "REN2_2") (pintype "bidirectional"))
      (node (ref "X2") (pin "18") (pinfunction "KL_18") (pintype "passive"))
    )
    (net (code "82") (name "ROM_SEL") (class "Default")
      (node (ref "IC4") (pin "57") (pinfunction "FB4MC17_57") (pintype "bidirectional"))
      (node (ref "R3") (pin "1") (pinfunction "1_1") (pintype "passive"))
      (node (ref "ROM") (pin "TP") (pinfunction "TP_TP") (pintype "input"))
    )
    (net (code "83") (name "R{slash}~{W}") (class "Default")
      (node (ref "HDR") (pin "22") (pinfunction "R/~{W}_22") (pintype "input"))
      (node (ref "IC1") (pin "22") (pinfunction "R/~{W}_22") (pintype "input"))
    )
    (net (code "84") (name "SRQ") (class "Default")
      (node (ref "IC3") (pin "12") (pinfunction "SRQ_12") (pintype "bidirectional"))
      (node (ref "IC4") (pin "34") (pinfunction "FB3MC6_34") (pintype "bidirectional"))
    )
    (net (code "85") (name "SRQ2") (class "Default")
      (node (ref "IC3") (pin "9") (pinfunction "SRQ2_9") (pintype "bidirectional"))
      (node (ref "X2") (pin "11") (pinfunction "KL_11") (pintype "passive"))
    )
    (net (code "86") (name "T{slash}~{R}") (class "Default")
      (node (ref "IC2") (pin "1") (pinfunction "TE_1") (pintype "input"))
      (node (ref "IC3") (pin "1") (pinfunction "TE_1") (pintype "input"))
      (node (ref "IC4") (pin "64") (pinfunction "FB2MC9-I/O/GSR_64") (pintype "bidirectional"))
    )
    (net (code "87") (name "VCC") (class "Default")
      (node (ref "C2") (pin "1") (pinfunction "1_1") (pintype "passive"))
      (node (ref "C2.1") (pin "1") (pinfunction "1_1") (pintype "passive"))
      (node (ref "C3.1") (pin "1") (pinfunction "1_1") (pintype "passive"))
      (node (ref "IC3") (pin "11") (pinfunction "DC_11") (pintype "input"))
      (node (ref "R3") (pin "2") (pinfunction "2_2") (pintype "passive"))
      (node (ref "VR1") (pin "3") (pinfunction "IN_3") (pintype "input"))
    )
    (net (code "88") (name "unconnected-(HDRA-CA2-Pad39)") (class "Default")
      (node (ref "HDR") (pin "39") (pinfunction "CA2_39") (pintype "bidirectional"))
    )
    (net (code "89") (name "unconnected-(HDRA-CB1-Pad18)") (class "Default")
      (node (ref "HDR") (pin "18") (pinfunction "CB1_18") (pintype "input"))
    )
    (net (code "90") (name "unconnected-(HDRA-CB2-Pad19)") (class "Default")
      (node (ref "HDR") (pin "19") (pinfunction "CB2_19") (pintype "bidirectional"))
    )
    (net (code "91") (name "unconnected-(HDRA-PA0-Pad2)") (class "Default")
      (node (ref "HDR") (pin "2") (pinfunction "PA0_2") (pintype "bidirectional"))
    )
    (net (code "92") (name "unconnected-(HDRA-PA1-Pad3)") (class "Default")
      (node (ref "HDR") (pin "3") (pinfunction "PA1_3") (pintype "bidirectional"))
    )
    (net (code "93") (name "unconnected-(HDRA-PA2-Pad4)") (class "Default")
      (node (ref "HDR") (pin "4") (pinfunction "PA2_4") (pintype "bidirectional"))
    )
    (net (code "94") (name "unconnected-(HDRA-PA3-Pad5)") (class "Default")
      (node (ref "HDR") (pin "5") (pinfunction "PA3_5") (pintype "bidirectional"))
    )
    (net (code "95") (name "unconnected-(HDRA-PA4-Pad6)") (class "Default")
      (node (ref "HDR") (pin "6") (pinfunction "PA4_6") (pintype "bidirectional"))
    )
    (net (code "96") (name "unconnected-(HDRA-PA5-Pad7)") (class "Default")
      (node (ref "HDR") (pin "7") (pinfunction "PA5_7") (pintype "bidirectional"))
    )
    (net (code "97") (name "unconnected-(HDRA-PA6-Pad8)") (class "Default")
      (node (ref "HDR") (pin "8") (pinfunction "PA6_8") (pintype "bidirectional"))
    )
    (net (code "98") (name "unconnected-(HDRA-PA7-Pad9)") (class "Default")
      (node (ref "HDR") (pin "9") (pinfunction "PA7_9") (pintype "bidirectional"))
    )
    (net (code "99") (name "unconnected-(IC4-FB2MC2-Pad60)") (class "Default")
      (node (ref "IC4") (pin "60") (pinfunction "FB2MC2_60") (pintype "bidirectional"))
    )
    (net (code "100") (name "unconnected-(IC4-FB2MC3-Pad58)") (class "Default")
      (node (ref "IC4") (pin "58") (pinfunction "FB2MC3_58") (pintype "bidirectional"))
    )
    (net (code "101") (name "unconnected-(IC4-FB2MC4-Pad59)") (class "Default")
      (node (ref "IC4") (pin "59") (pinfunction "FB2MC4_59") (pintype "bidirectional"))
    )
    (net (code "102") (name "unconnected-(IC4-FB2MC5-Pad61)") (class "Default")
      (node (ref "IC4") (pin "61") (pinfunction "FB2MC5_61") (pintype "bidirectional"))
    )
    (net (code "103") (name "~{CS2}") (class "Default")
      (node (ref "HDR") (pin "23") (pinfunction "~{CS2}_23") (pintype "input"))
      (node (ref "IC1") (pin "23") (pinfunction "~{CS2}_23") (pintype "input"))
    )
    (net (code "104") (name "~{IRQ}") (class "Default")
      (node (ref "HDR") (pin "21") (pinfunction "~{IRQ}_21") (pintype "open_collector"))
      (node (ref "IC1") (pin "21") (pinfunction "~{IRQ}_21") (pintype "open_collector"))
    )
    (net (code "105") (name "~{RESET}") (class "Default")
      (node (ref "HDR") (pin "34") (pinfunction "~{RESET}_34") (pintype "input"))
      (node (ref "IC1") (pin "34") (pinfunction "~{RESET}_34") (pintype "input"))
      (node (ref "IC4") (pin "62") (pinfunction "FB2MC6_62") (pintype "bidirectional"))
    )
  )
)
